# placasensores.net
KiCad netlist of a schematic drawn in EAGLE
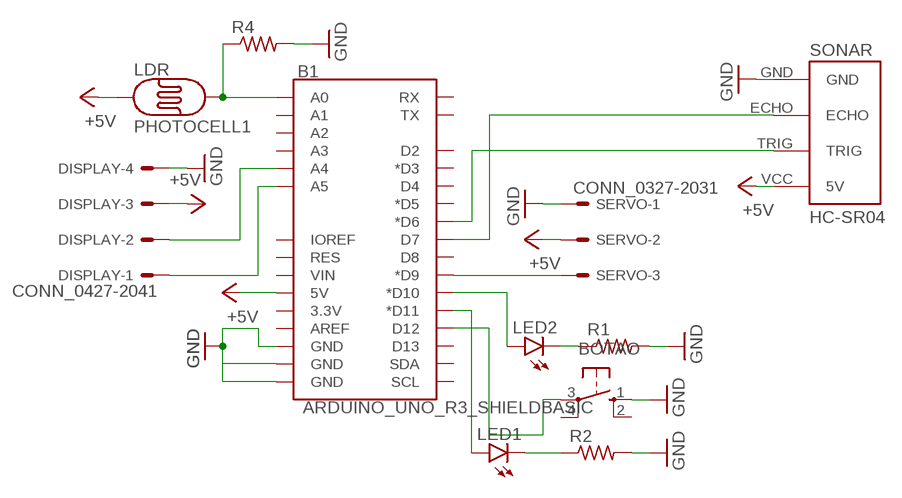
[diagram p0: schematic, sheet 1]

(export (version "E")
  (design (tool "Eeschema 10.0.6"))
  (components
    (comp (ref "B1")
      (value "ARDUINO_UNO_R3_SHIELDBASIC")
      (footprint "eagle-import:UNO_R3_SHIELD")
      (libsource (lib "eagle-import") (part "ARDUINO_UNO_R3_SHIELDBASIC"))
    )
    (comp (ref "BOTAO")
      (value "10-XX")
      (footprint "eagle-import:B3F-10XX")
      (fields (field (name "MPN") "B3F-1000"))
      (libsource (lib "eagle-import") (part "10-XX"))
    )
    (comp (ref "DISPLAY")
      (value "CONN_0427-2041")
      (footprint "eagle-import:6410-04")
      (libsource (lib "eagle-import") (part "CONN_0427-2041"))
    )
    (comp (ref "LDR")
      (value "PHOTOCELL1")
      (footprint "eagle-import:LDR_OFFBOARD")
      (libsource (lib "eagle-import") (part "PHOTOCELL1"))
    )
    (comp (ref "LED1")
      (value "LED5MM")
      (footprint "eagle-import:LED5MM")
      (libsource (lib "eagle-import") (part "LED5MM"))
    )
    (comp (ref "LED2")
      (value "LED5MM")
      (footprint "eagle-import:LED5MM")
      (libsource (lib "eagle-import") (part "LED5MM"))
    )
    (comp (ref "R1")
      (value "R-US_0204/5")
      (footprint "eagle-import:0204_5")
      (libsource (lib "eagle-import") (part "R-US_0204/5"))
    )
    (comp (ref "R2")
      (value "R-US_0204/5")
      (footprint "eagle-import:0204_5")
      (libsource (lib "eagle-import") (part "R-US_0204/5"))
    )
    (comp (ref "R4")
      (value "R-US_0204/5")
      (footprint "eagle-import:0204_5")
      (libsource (lib "eagle-import") (part "R-US_0204/5"))
    )
    (comp (ref "SERVO")
      (value "CONN_0327-2031")
      (footprint "eagle-import:6410-03")
      (libsource (lib "eagle-import") (part "CONN_0327-2031"))
    )
    (comp (ref "SONAR")
      (value "HC-SR04")
      (footprint "eagle-import:HC-SR04_FOOTPRINT")
      (libsource (lib "eagle-import") (part "HC-SR04"))
    )
  )
  (nets
    (net (code "1") (name "+5V") (class "Default")
      (node (ref "B1") (pin "5V") (pinfunction "5V_5V") (pintype "bidirectional"))
      (node (ref "DISPLAY") (pin "3") (pinfunction "S_3") (pintype "passive"))
      (node (ref "LDR") (pin "1") (pinfunction "P$1_1") (pintype "bidirectional"))
      (node (ref "SERVO") (pin "2") (pinfunction "S_2") (pintype "passive"))
      (node (ref "SONAR") (pin "VCC") (pinfunction "5V_VCC") (pintype "bidirectional"))
    )
    (net (code "2") (name "GND") (class "Default")
      (node (ref "B1") (pin "GND@0") (pinfunction "GND_GND@0") (pintype "bidirectional"))
      (node (ref "B1") (pin "GND@1") (pinfunction "GND_GND@1") (pintype "bidirectional"))
      (node (ref "B1") (pin "GND@2") (pinfunction "GND_GND@2") (pintype "bidirectional"))
      (node (ref "BOTAO") (pin "1") (pinfunction "S_1") (pintype "passive"))
      (node (ref "DISPLAY") (pin "4") (pinfunction "S_4") (pintype "passive"))
      (node (ref "R1") (pin "2") (pinfunction "2_2") (pintype "passive"))
      (node (ref "R2") (pin "2") (pinfunction "2_2") (pintype "passive"))
      (node (ref "R4") (pin "2") (pinfunction "2_2") (pintype "passive"))
      (node (ref "SERVO") (pin "1") (pinfunction "S_1") (pintype "passive"))
      (node (ref "SONAR") (pin "GND") (pinfunction "GND_GND") (pintype "bidirectional"))
    )
    (net (code "3") (name "Net-(B1-*D6)") (class "Default")
      (node (ref "B1") (pin "D6") (pinfunction "*D6_D6") (pintype "bidirectional"))
      (node (ref "SONAR") (pin "TRIG") (pinfunction "TRIG_TRIG") (pintype "bidirectional"))
    )
    (net (code "4") (name "Net-(B1-*D9)") (class "Default")
      (node (ref "B1") (pin "D9") (pinfunction "*D9_D9") (pintype "bidirectional"))
      (node (ref "SERVO") (pin "3") (pinfunction "S_3") (pintype "passive"))
    )
    (net (code "5") (name "Net-(B1-*D10)") (class "Default")
      (node (ref "B1") (pin "D10") (pinfunction "*D10_D10") (pintype "bidirectional"))
      (node (ref "LED2") (pin "A") (pinfunction "A_A") (pintype "passive"))
    )
    (net (code "6") (name "Net-(B1-*D11)") (class "Default")
      (node (ref "B1") (pin "D11") (pinfunction "*D11_D11") (pintype "bidirectional"))
      (node (ref "LED1") (pin "A") (pinfunction "A_A") (pintype "passive"))
    )
    (net (code "7") (name "Net-(B1-PadD7)") (class "Default")
      (node (ref "B1") (pin "D7") (pinfunction "D7_D7") (pintype "bidirectional"))
      (node (ref "SONAR") (pin "ECHO") (pinfunction "ECHO_ECHO") (pintype "bidirectional"))
    )
    (net (code "8") (name "Net-(BOTAO-P)") (class "Default")
      (node (ref "B1") (pin "D12") (pinfunction "D12_D12") (pintype "bidirectional"))
      (node (ref "BOTAO") (pin "3") (pinfunction "P_3") (pintype "passive"))
    )
    (net (code "9") (name "Net-(DISPLAYA-S)") (class "Default")
      (node (ref "B1") (pin "A5") (pinfunction "A5_A5") (pintype "bidirectional"))
      (node (ref "DISPLAY") (pin "1") (pinfunction "S_1") (pintype "passive"))
    )
    (net (code "10") (name "Net-(DISPLAYB-S)") (class "Default")
      (node (ref "B1") (pin "A4") (pinfunction "A4_A4") (pintype "bidirectional"))
      (node (ref "DISPLAY") (pin "2") (pinfunction "S_2") (pintype "passive"))
    )
    (net (code "11") (name "Net-(LDR-P$2)") (class "Default")
      (node (ref "B1") (pin "A0") (pinfunction "A0_A0") (pintype "bidirectional"))
      (node (ref "LDR") (pin "2") (pinfunction "P$2_2") (pintype "bidirectional"))
      (node (ref "R4") (pin "1") (pinfunction "1_1") (pintype "passive"))
    )
    (net (code "12") (name "Net-(LED1-C)") (class "Default")
      (node (ref "LED1") (pin "K") (pinfunction "C_K") (pintype "passive"))
      (node (ref "R2") (pin "1") (pinfunction "1_1") (pintype "passive"))
    )
    (net (code "13") (name "Net-(LED2-C)") (class "Default")
      (node (ref "LED2") (pin "K") (pinfunction "C_K") (pintype "passive"))
      (node (ref "R1") (pin "1") (pinfunction "1_1") (pintype "passive"))
    )
    (net (code "14") (name "unconnected-(B1-*D3-PadD3)") (class "Default")
      (node (ref "B1") (pin "D3") (pinfunction "*D3_D3") (pintype "bidirectional"))
    )
    (net (code "15") (name "unconnected-(B1-*D5-PadD5)") (class "Default")
      (node (ref "B1") (pin "D5") (pinfunction "*D5_D5") (pintype "bidirectional"))
    )
    (net (code "16") (name "unconnected-(B1-Pad3.3V)") (class "Default")
      (node (ref "B1") (pin "3.3V") (pinfunction "3.3V_3.3V") (pintype "bidirectional"))
    )
    (net (code "17") (name "unconnected-(B1-PadA1)") (class "Default")
      (node (ref "B1") (pin "A1") (pinfunction "A1_A1") (pintype "bidirectional"))
    )
    (net (code "18") (name "unconnected-(B1-PadA2)") (class "Default")
      (node (ref "B1") (pin "A2") (pinfunction "A2_A2") (pintype "bidirectional"))
    )
    (net (code "19") (name "unconnected-(B1-PadA3)") (class "Default")
      (node (ref "B1") (pin "A3") (pinfunction "A3_A3") (pintype "bidirectional"))
    )
    (net (code "20") (name "unconnected-(B1-PadAREF)") (class "Default")
      (node (ref "B1") (pin "AREF") (pinfunction "AREF_AREF") (pintype "bidirectional"))
    )
    (net (code "21") (name "unconnected-(B1-PadD2)") (class "Default")
      (node (ref "B1") (pin "D2") (pinfunction "D2_D2") (pintype "bidirectional"))
    )
    (net (code "22") (name "unconnected-(B1-PadD4)") (class "Default")
      (node (ref "B1") (pin "D4") (pinfunction "D4_D4") (pintype "bidirectional"))
    )
    (net (code "23") (name "unconnected-(B1-PadD8)") (class "Default")
      (node (ref "B1") (pin "D8") (pinfunction "D8_D8") (pintype "bidirectional"))
    )
    (net (code "24") (name "unconnected-(B1-PadD13)") (class "Default")
      (node (ref "B1") (pin "D13") (pinfunction "D13_D13") (pintype "bidirectional"))
    )
    (net (code "25") (name "unconnected-(B1-PadIOREF)") (class "Default")
      (node (ref "B1") (pin "IOREF") (pinfunction "IOREF_IOREF") (pintype "bidirectional"))
    )
    (net (code "26") (name "unconnected-(B1-PadRES)") (class "Default")
      (node (ref "B1") (pin "RES") (pinfunction "RES_RES") (pintype "bidirectional"))
    )
    (net (code "27") (name "unconnected-(B1-PadRX)") (class "Default")
      (node (ref "B1") (pin "RX") (pinfunction "RX_RX") (pintype "bidirectional"))
    )
    (net (code "28") (name "unconnected-(B1-PadSCL)") (class "Default")
      (node (ref "B1") (pin "SCL") (pinfunction "SCL_SCL") (pintype "bidirectional"))
    )
    (net (code "29") (name "unconnected-(B1-PadSDA)") (class "Default")
      (node (ref "B1") (pin "SDA") (pinfunction "SDA_SDA") (pintype "bidirectional"))
    )
    (net (code "30") (name "unconnected-(B1-PadTX)") (class "Default")
      (node (ref "B1") (pin "TX") (pinfunction "TX_TX") (pintype "bidirectional"))
    )
    (net (code "31") (name "unconnected-(B1-PadVIN)") (class "Default")
      (node (ref "B1") (pin "VIN") (pinfunction "VIN_VIN") (pintype "bidirectional"))
    )
    (net (code "32") (name "unconnected-(BOTAO-P1-Pad4)") (class "Default")
      (node (ref "BOTAO") (pin "4") (pinfunction "P1_4") (pintype "passive"))
    )
    (net (code "33") (name "unconnected-(BOTAO-S1-Pad2)") (class "Default")
      (node (ref "BOTAO") (pin "2") (pinfunction "S1_2") (pintype "passive"))
    )
  )
)
